# rtd_interface_MAX31865.net
KiCad netlist of a schematic drawn in Altium Designer
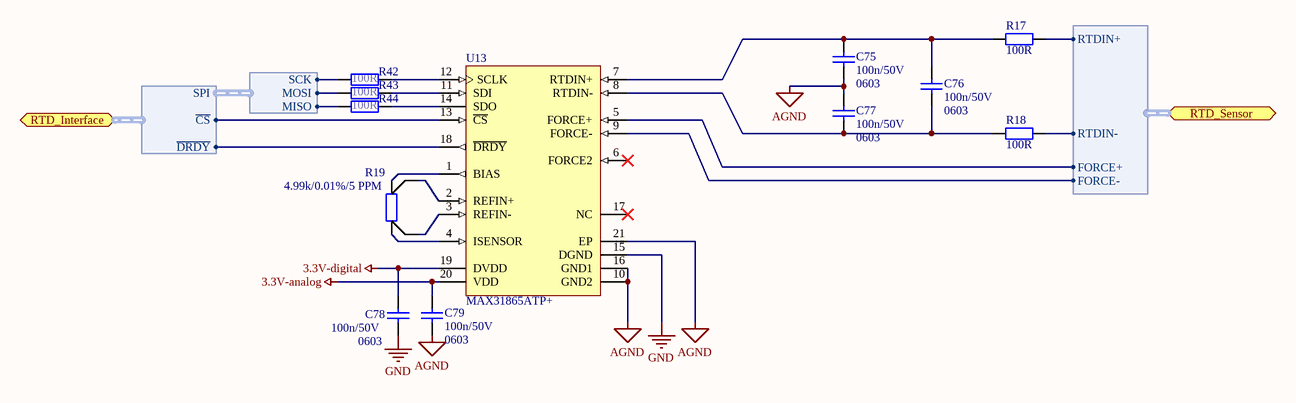
[diagram p0: rtd_interface_MAX31865.SchDoc]

(export (version "E")
  (design (tool "Eeschema 10.0.6"))
  (components
    (comp (ref "C75")
      (value "100n/50V")
      (footprint "SMD_Capacitor_0603")
      (description "Ceramic Cap Kemet COTS 100n/50V X7R 0603")
      (fields
        (field (name "MANUFACTURER") "Kemet")
        (field (name "MANUFACTURERPARTNUMBER") "C0603T104K5RALTU")
        (field (name "PACKAGE") "0603")
      )
      (libsource (lib "capacitors") (part "Cer_C0603T104K5RALTU"))
    )
    (comp (ref "C76")
      (value "100n/50V")
      (footprint "SMD_Capacitor_0603")
      (description "Ceramic Cap Kemet COTS 100n/50V X7R 0603")
      (fields
        (field (name "MANUFACTURER") "Kemet")
        (field (name "MANUFACTURERPARTNUMBER") "C0603T104K5RALTU")
        (field (name "PACKAGE") "0603")
      )
      (libsource (lib "capacitors") (part "Cer_C0603T104K5RALTU"))
    )
    (comp (ref "C77")
      (value "100n/50V")
      (footprint "SMD_Capacitor_0603")
      (description "Ceramic Cap Kemet COTS 100n/50V X7R 0603")
      (fields
        (field (name "MANUFACTURER") "Kemet")
        (field (name "MANUFACTURERPARTNUMBER") "C0603T104K5RALTU")
        (field (name "PACKAGE") "0603")
      )
      (libsource (lib "capacitors") (part "Cer_C0603T104K5RALTU"))
    )
    (comp (ref "C78")
      (value "100n/50V")
      (footprint "SMD_Capacitor_0603")
      (description "Ceramic Cap Kemet COTS 100n/50V X7R 0603")
      (fields
        (field (name "MANUFACTURER") "Kemet")
        (field (name "MANUFACTURERPARTNUMBER") "C0603T104K5RALTU")
        (field (name "PACKAGE") "0603")
      )
      (libsource (lib "capacitors") (part "Cer_C0603T104K5RALTU"))
    )
    (comp (ref "C79")
      (value "100n/50V")
      (footprint "SMD_Capacitor_0603")
      (description "Ceramic Cap Kemet COTS 100n/50V X7R 0603")
      (fields
        (field (name "MANUFACTURER") "Kemet")
        (field (name "MANUFACTURERPARTNUMBER") "C0603T104K5RALTU")
        (field (name "PACKAGE") "0603")
      )
      (libsource (lib "capacitors") (part "Cer_C0603T104K5RALTU"))
    )
    (comp (ref "R17")
      (value "100R")
      (footprint "0603")
      (description "Generic resistor")
      (libsource (lib "GG") (part "Res"))
    )
    (comp (ref "R18")
      (value "100R")
      (footprint "0603")
      (description "Generic resistor")
      (libsource (lib "GG") (part "Res"))
    )
    (comp (ref "R19")
      (value "4.99k/0.01%/5 PPM")
      (footprint "0603_shunt")
      (description "Generic shunt resistor")
      (libsource (lib "GG") (part "Res_Shunt"))
    )
    (comp (ref "R42")
      (value "100R")
      (footprint "0603")
      (description "Generic resistor")
      (libsource (lib "GG") (part "Res"))
    )
    (comp (ref "R43")
      (value "100R")
      (footprint "0603")
      (description "Generic resistor")
      (libsource (lib "GG") (part "Res"))
    )
    (comp (ref "R44")
      (value "100R")
      (footprint "0603")
      (description "Generic resistor")
      (libsource (lib "GG") (part "Res"))
    )
    (comp (ref "U13")
      (value "MAX31865ATP+")
      (footprint "MAXM-T2055+5_M")
      (fields (field (name "GENERIC PART NUMBER") "MAX31865"))
      (libsource (lib "Maxim Sensors") (part "MAX31865ATP+"))
    )
  )
  (nets
    (net (code "4") (name "/FORCE+") (class "Default")
      (node (ref "U13") (pin "5") (pinfunction "FORCE+_5") (pintype "input"))
    )
    (net (code "5") (name "/FORCE-") (class "Default")
      (node (ref "U13") (pin "9") (pinfunction "FORCE-_9") (pintype "input"))
    )
    (net (code "6") (name "/MISO") (class "Default")
      (node (ref "R44") (pin "1") (pinfunction "1_1") (pintype "passive"))
    )
    (net (code "7") (name "/MOSI") (class "Default")
      (node (ref "R43") (pin "1") (pinfunction "1_1") (pintype "passive"))
    )
    (net (code "8") (name "/RTDIN+") (class "Default")
      (node (ref "R17") (pin "2") (pinfunction "2_2") (pintype "passive"))
    )
    (net (code "9") (name "/RTDIN-") (class "Default")
      (node (ref "R18") (pin "2") (pinfunction "2_2") (pintype "passive"))
    )
    (net (code "10") (name "/SCK") (class "Default")
      (node (ref "R42") (pin "1") (pinfunction "1_1") (pintype "passive"))
    )
    (net (code "14") (name "/~{CS}") (class "Default")
      (node (ref "U13") (pin "13") (pinfunction "~{CS}_13") (pintype "input"))
    )
    (net (code "15") (name "/~{DRDY}") (class "Default")
      (node (ref "U13") (pin "18") (pinfunction "~{DRDY}_18") (pintype "output"))
    )
    (net (code "16") (name "3.3V-analog") (class "Default")
      (node (ref "C79") (pin "1") (pinfunction "1_1") (pintype "passive"))
      (node (ref "U13") (pin "20") (pinfunction "VDD_20") (pintype "power_in"))
    )
    (net (code "17") (name "3.3V-digital") (class "Default")
      (node (ref "C78") (pin "1") (pinfunction "1_1") (pintype "passive"))
      (node (ref "U13") (pin "19") (pinfunction "DVDD_19") (pintype "power_in"))
    )
    (net (code "18") (name "AGND") (class "Default")
      (node (ref "C75") (pin "1") (pinfunction "1_1") (pintype "passive"))
      (node (ref "C77") (pin "2") (pinfunction "2_2") (pintype "passive"))
      (node (ref "C79") (pin "2") (pinfunction "2_2") (pintype "passive"))
      (node (ref "U13") (pin "10") (pinfunction "GND2_10") (pintype "power_in"))
      (node (ref "U13") (pin "16") (pinfunction "GND1_16") (pintype "power_in"))
      (node (ref "U13") (pin "21") (pinfunction "EP_21") (pintype "power_in"))
    )
    (net (code "19") (name "GND") (class "Default")
      (node (ref "C78") (pin "2") (pinfunction "2_2") (pintype "passive"))
      (node (ref "U13") (pin "15") (pinfunction "DGND_15") (pintype "power_in"))
    )
    (net (code "20") (name "Net-(U13-BIAS)") (class "Default")
      (node (ref "R19") (pin "1") (pinfunction "1_1") (pintype "passive"))
      (node (ref "U13") (pin "1") (pinfunction "BIAS_1") (pintype "output"))
    )
    (net (code "21") (name "Net-(U13-ISENSOR)") (class "Default")
      (node (ref "R19") (pin "4") (pinfunction "4_4") (pintype "passive"))
      (node (ref "U13") (pin "4") (pinfunction "ISENSOR_4") (pintype "input"))
    )
    (net (code "22") (name "Net-(U13-REFIN+)") (class "Default")
      (node (ref "R19") (pin "2") (pinfunction "2_2") (pintype "passive"))
      (node (ref "U13") (pin "2") (pinfunction "REFIN+_2") (pintype "input"))
    )
    (net (code "23") (name "Net-(U13-REFIN-)") (class "Default")
      (node (ref "R19") (pin "3") (pinfunction "3_3") (pintype "passive"))
      (node (ref "U13") (pin "3") (pinfunction "REFIN-_3") (pintype "input"))
    )
    (net (code "24") (name "Net-(U13-RTDIN+)") (class "Default")
      (node (ref "C75") (pin "2") (pinfunction "2_2") (pintype "passive"))
      (node (ref "C76") (pin "2") (pinfunction "2_2") (pintype "passive"))
      (node (ref "R17") (pin "1") (pinfunction "1_1") (pintype "passive"))
      (node (ref "U13") (pin "7") (pinfunction "RTDIN+_7") (pintype "input"))
    )
    (net (code "25") (name "Net-(U13-RTDIN-)") (class "Default")
      (node (ref "C76") (pin "1") (pinfunction "1_1") (pintype "passive"))
      (node (ref "C77") (pin "1") (pinfunction "1_1") (pintype "passive"))
      (node (ref "R18") (pin "1") (pinfunction "1_1") (pintype "passive"))
      (node (ref "U13") (pin "8") (pinfunction "RTDIN-_8") (pintype "input"))
    )
    (net (code "26") (name "Net-(U13-SCLK)") (class "Default")
      (node (ref "R42") (pin "2") (pinfunction "2_2") (pintype "passive"))
      (node (ref "U13") (pin "12") (pinfunction "SCLK_12") (pintype "input"))
    )
    (net (code "27") (name "Net-(U13-SDI)") (class "Default")
      (node (ref "R43") (pin "2") (pinfunction "2_2") (pintype "passive"))
      (node (ref "U13") (pin "11") (pinfunction "SDI_11") (pintype "input"))
    )
    (net (code "28") (name "Net-(U13-SDO)") (class "Default")
      (node (ref "R44") (pin "2") (pinfunction "2_2") (pintype "passive"))
      (node (ref "U13") (pin "14") (pinfunction "SDO_14") (pintype "tri_state"))
    )
    (net (code "29") (name "unconnected-(U13-FORCE2-Pad6)") (class "Default")
      (node (ref "U13") (pin "6") (pinfunction "FORCE2_6") (pintype "input+no_connect"))
    )
    (net (code "30") (name "unconnected-(U13-NC-Pad17)") (class "Default")
      (node (ref "U13") (pin "17") (pinfunction "NC_17") (pintype "passive+no_connect"))
    )
  )
)
